# DE-160724.net
KiCad netlist of a schematic drawn in Altium Designer
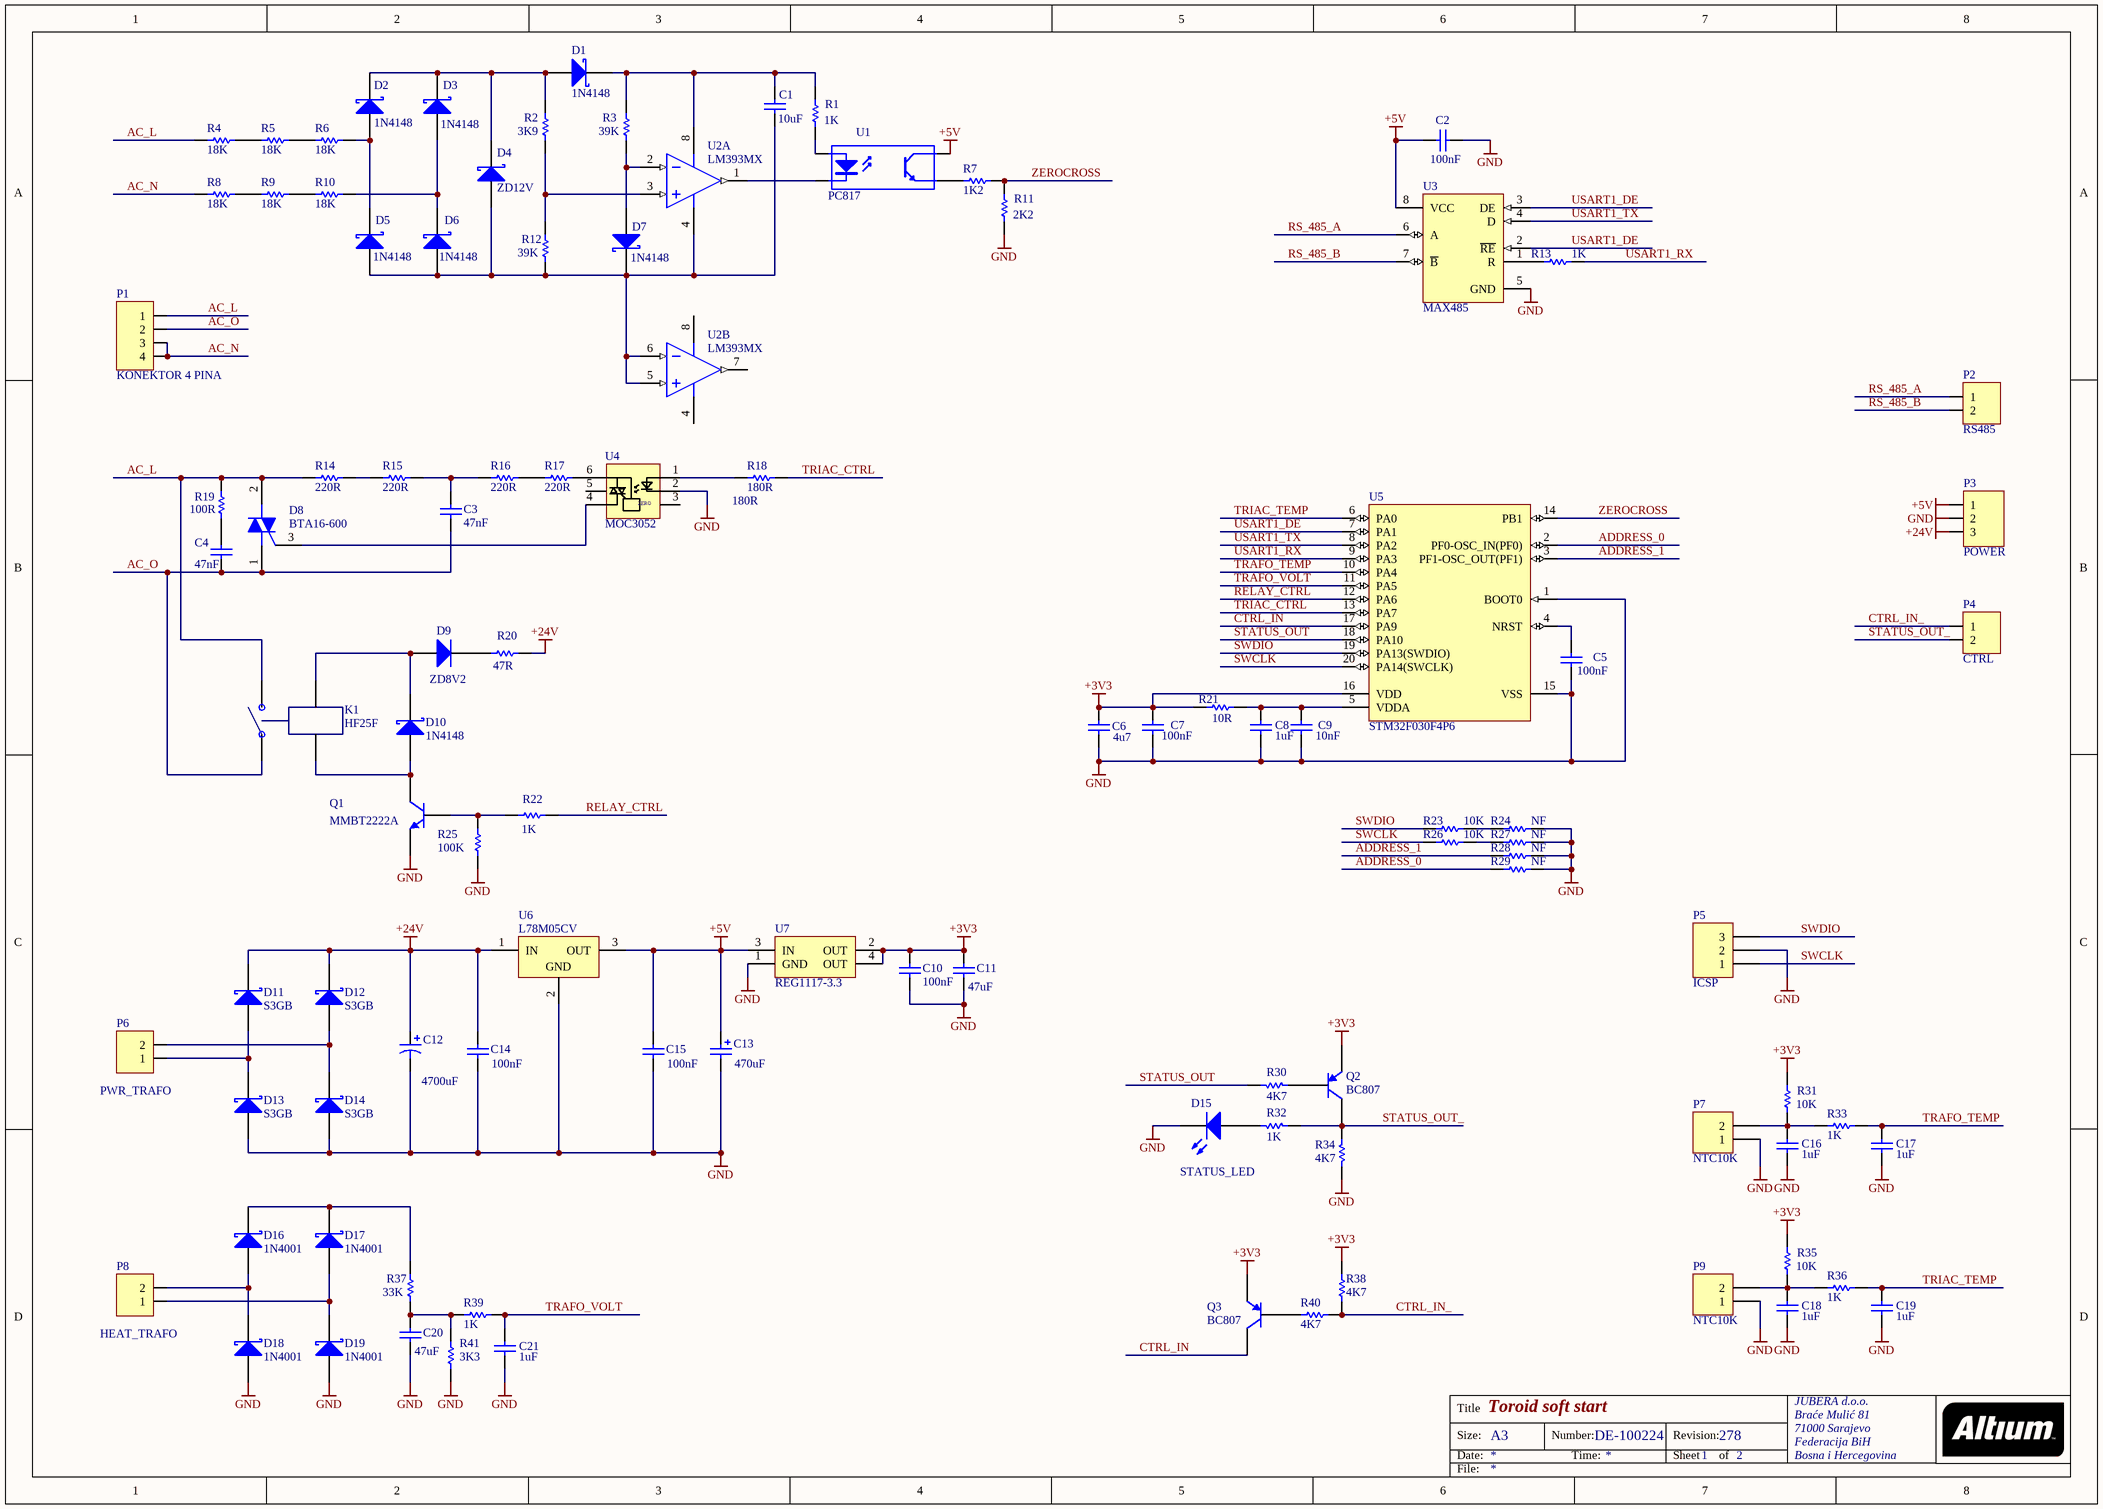
[diagram p0: DE-160724.SchDoc]

(export (version "E")
  (design (tool "Eeschema 10.0.6"))
  (components
    (comp (ref "C1")
      (value "10uF")
      (footprint "0805")
      (description "Ceramic Chip Capacitor - Standard")
      (fields (field (name "PUBLISHER") "Altium Limited"))
      (libsource (lib "DE-100224") (part "C0805"))
    )
    (comp (ref "C2")
      (value "100nF")
      (footprint "0603")
      (description "Ceramic Chip Capacitor - Standard")
      (fields (field (name "PUBLISHER") "Altium Limited"))
      (libsource (lib "KEMET Chip Capacitor") (part "C0603"))
    )
    (comp (ref "C3")
      (value "47nF")
      (footprint "X2 CAP")
      (description "X2 275VAC capaitor")
      (libsource (lib "DE-100224") (part "CAP X2"))
    )
    (comp (ref "C4")
      (value "47nF")
      (footprint "X2 CAP")
      (description "X2 275VAC capaitor")
      (libsource (lib "DE-100224") (part "CAP X2"))
    )
    (comp (ref "C5")
      (value "100nF")
      (footprint "0603")
      (description "Ceramic Chip Capacitor - Standard")
      (fields (field (name "PUBLISHER") "Altium Limited"))
      (libsource (lib "KEMET Chip Capacitor") (part "C0603"))
    )
    (comp (ref "C6")
      (value "4u7")
      (footprint "0805")
      (description "Ceramic Chip Capacitor - Standard")
      (fields (field (name "PUBLISHER") "Altium Limited"))
      (libsource (lib "KEMET Chip Capacitor") (part "C0805"))
    )
    (comp (ref "C7")
      (value "100nF")
      (footprint "0603")
      (description "Ceramic Chip Capacitor - Standard")
      (fields (field (name "PUBLISHER") "Altium Limited"))
      (libsource (lib "KEMET Chip Capacitor") (part "C0603"))
    )
    (comp (ref "C8")
      (value "1uF")
      (footprint "0603")
      (description "Ceramic Chip Capacitor - Standard")
      (fields (field (name "PUBLISHER") "Altium Limited"))
      (libsource (lib "KEMET Chip Capacitor") (part "C0603"))
    )
    (comp (ref "C9")
      (value "10nF")
      (footprint "0603")
      (description "Ceramic Chip Capacitor - Standard")
      (fields (field (name "PUBLISHER") "Altium Limited"))
      (libsource (lib "KEMET Chip Capacitor") (part "C0603"))
    )
    (comp (ref "C10")
      (value "100nF")
      (footprint "0603")
      (description "Ceramic Chip Capacitor - Standard")
      (fields (field (name "PUBLISHER") "Altium Limited"))
      (libsource (lib "DE-251215") (part "C0603"))
    )
    (comp (ref "C11")
      (value "47uF")
      (footprint "1206")
      (description "Ceramic Chip Capacitor - Standard")
      (fields (field (name "Comment") "C1206") (field (name "PUBLISHER") "Altium Limited"))
      (libsource (lib "DE-160724") (part "C1206"))
    )
    (comp (ref "C12")
      (value "4700uF")
      (footprint "CAPPR5-13X25")
      (description "Aluminum Electrolytic Capacitor, Radial Style with Long Leads: 4700uF, 10V")
      (fields (field (name "PUBLISHER") "Altium Limited"))
      (libsource (lib "Vishay Roederstein Electrolytic Radial-Lead Capacitor") (part "EKA00GG447C00"))
    )
    (comp (ref "C13")
      (value "470uF")
      (footprint "CAPPR5-10X16")
      (description "Aluminum Electrolytic Capacitor, Radial Style with Long Leads: 470uF, 35V")
      (fields (field (name "PUBLISHER") "Altium Limited"))
      (libsource (lib "DE-100224") (part "EKA00DD347F00"))
    )
    (comp (ref "C14")
      (value "100nF")
      (footprint "0603")
      (description "Ceramic Chip Capacitor - Standard")
      (fields (field (name "PUBLISHER") "Altium Limited"))
      (libsource (lib "DE-100224") (part "C0603"))
    )
    (comp (ref "C15")
      (value "100nF")
      (footprint "0603")
      (description "Ceramic Chip Capacitor - Standard")
      (fields (field (name "PUBLISHER") "Altium Limited"))
      (libsource (lib "DE-100224") (part "C0603"))
    )
    (comp (ref "C16")
      (value "1uF")
      (footprint "0603")
      (description "Ceramic Chip Capacitor - Standard")
      (fields (field (name "PUBLISHER") "Altium Limited"))
      (libsource (lib "KEMET Chip Capacitor") (part "C0603"))
    )
    (comp (ref "C17")
      (value "1uF")
      (footprint "0603")
      (description "Ceramic Chip Capacitor - Standard")
      (fields (field (name "PUBLISHER") "Altium Limited"))
      (libsource (lib "KEMET Chip Capacitor") (part "C0603"))
    )
    (comp (ref "C18")
      (value "1uF")
      (footprint "0603")
      (description "Ceramic Chip Capacitor - Standard")
      (fields (field (name "PUBLISHER") "Altium Limited"))
      (libsource (lib "KEMET Chip Capacitor") (part "C0603"))
    )
    (comp (ref "C19")
      (value "1uF")
      (footprint "0603")
      (description "Ceramic Chip Capacitor - Standard")
      (fields (field (name "PUBLISHER") "Altium Limited"))
      (libsource (lib "KEMET Chip Capacitor") (part "C0603"))
    )
    (comp (ref "C20")
      (value "47uF")
      (footprint "1206")
      (description "Ceramic Chip Capacitor - Standard")
      (fields (field (name "Comment") "C1206") (field (name "PUBLISHER") "Altium Limited"))
      (libsource (lib "DE-160724") (part "C1206"))
    )
    (comp (ref "C21")
      (value "1uF")
      (footprint "0603")
      (description "Ceramic Chip Capacitor - Standard")
      (fields (field (name "PUBLISHER") "Altium Limited"))
      (libsource (lib "KEMET Chip Capacitor") (part "C0603"))
    )
    (comp (ref "D1")
      (value "1N4148")
      (footprint "SOD323")
      (description "Schottky Barrier Diode")
      (fields (field (name "PUBLISHER") "Altium Limited"))
      (libsource (lib "DE-100224") (part "1PS76SB10"))
    )
    (comp (ref "D2")
      (value "1N4148")
      (footprint "SOD323")
      (description "Schottky Barrier Diode")
      (fields (field (name "PUBLISHER") "Altium Limited"))
      (libsource (lib "DE-100224") (part "1PS76SB10"))
    )
    (comp (ref "D3")
      (value "1N4148")
      (footprint "SOD323")
      (description "Schottky Barrier Diode")
      (fields (field (name "PUBLISHER") "Altium Limited"))
      (libsource (lib "DE-100224") (part "1PS76SB10"))
    )
    (comp (ref "D4")
      (value "ZD12V")
      (footprint "SMB")
      (description "Schottky Rectifier")
      (fields (field (name "PUBLISHER") "Altium Limited"))
      (libsource (lib "DE-100224") (part "10BQ100"))
    )
    (comp (ref "D5")
      (value "1N4148")
      (footprint "SOD323")
      (description "Schottky Barrier Diode")
      (fields (field (name "PUBLISHER") "Altium Limited"))
      (libsource (lib "DE-100224") (part "1PS76SB10"))
    )
    (comp (ref "D6")
      (value "1N4148")
      (footprint "SOD323")
      (description "Schottky Barrier Diode")
      (fields (field (name "PUBLISHER") "Altium Limited"))
      (libsource (lib "DE-100224") (part "1PS76SB10"))
    )
    (comp (ref "D7")
      (value "1N4148")
      (footprint "SOD323")
      (description "Schottky Barrier Diode")
      (fields (field (name "PUBLISHER") "Altium Limited"))
      (libsource (lib "DE-100224") (part "1PS76SB10"))
    )
    (comp (ref "D8")
      (value "BTA16-600")
      (footprint "ONSC-TO-220-3-221A-07")
      (description "Triacs, Silicon Bidirectional Thyristor, 3-Pin TO-220, Pb-Free, Tube")
      (fields (field (name "MANUFACTURER") "On Semiconductor") (field (name "PARTNUMBER") "BTA08-600BW3G"))
      (libsource (lib "DE-100224") (part "BTA08-600BW3G"))
    )
    (comp (ref "D9")
      (value "ZD8V2")
      (footprint "DO-41")
      (description "1.0 Ampere General Purpose Rectifier")
      (fields (field (name "PUBLISHER") "Altium Limited"))
      (libsource (lib "DE-100224") (part "1N4003"))
    )
    (comp (ref "D10")
      (value "1N4148")
      (footprint "SOD323")
      (description "Schottky Barrier Diode")
      (fields (field (name "PUBLISHER") "Altium Limited"))
      (libsource (lib "DE-100224") (part "1PS76SB10"))
    )
    (comp (ref "D11")
      (value "S3GB")
      (footprint "SMB")
      (description "Schottky Diode")
      (fields (field (name "PUBLISHER") "Altium Limited"))
      (libsource (lib "Miscellaneous Devices") (part "D Schottky"))
    )
    (comp (ref "D12")
      (value "S3GB")
      (footprint "SMB")
      (description "Schottky Diode")
      (fields (field (name "PUBLISHER") "Altium Limited"))
      (libsource (lib "Miscellaneous Devices") (part "D Schottky"))
    )
    (comp (ref "D13")
      (value "S3GB")
      (footprint "SMB")
      (description "Schottky Diode")
      (fields (field (name "PUBLISHER") "Altium Limited"))
      (libsource (lib "Miscellaneous Devices") (part "D Schottky"))
    )
    (comp (ref "D14")
      (value "S3GB")
      (footprint "SMB")
      (description "Schottky Diode")
      (fields (field (name "PUBLISHER") "Altium Limited"))
      (libsource (lib "Miscellaneous Devices") (part "D Schottky"))
    )
    (comp (ref "D15")
      (value "STATUS_LED")
      (footprint "1.6X0.8X0.8")
      (description "Blue Surface Mount Chip LED, Blue")
      (fields (field (name "PUBLISHER") "Altium Limited"))
      (libsource (lib "DE-160724") (part "HSMB-C190"))
    )
    (comp (ref "D16")
      (value "1N4001")
      (footprint "SMB")
      (description "Schottky Diode")
      (fields (field (name "PUBLISHER") "Altium Limited"))
      (libsource (lib "Miscellaneous Devices") (part "D Schottky"))
    )
    (comp (ref "D17")
      (value "1N4001")
      (footprint "SMB")
      (description "Schottky Diode")
      (fields (field (name "PUBLISHER") "Altium Limited"))
      (libsource (lib "Miscellaneous Devices") (part "D Schottky"))
    )
    (comp (ref "D18")
      (value "1N4001")
      (footprint "SMB")
      (description "Schottky Diode")
      (fields (field (name "PUBLISHER") "Altium Limited"))
      (libsource (lib "Miscellaneous Devices") (part "D Schottky"))
    )
    (comp (ref "D19")
      (value "1N4001")
      (footprint "SMB")
      (description "Schottky Diode")
      (fields (field (name "PUBLISHER") "Altium Limited"))
      (libsource (lib "Miscellaneous Devices") (part "D Schottky"))
    )
    (comp (ref "K1")
      (value "HF25F")
      (footprint "HF25F")
      (description "PCB relay 250VAC/20A 30VDC/16A")
      (libsource (lib "DE-100224") (part "HF25F"))
    )
    (comp (ref "P1")
      (value "KONEKTOR 4 PINA")
      (footprint "KONEKTOR 4 PINA")
      (description "Razdvojivi konektor 4 pina")
      (libsource (lib "DE-100224") (part "KONEKTOR 4 PINA"))
    )
    (comp (ref "P2")
      (value "RS485")
      (footprint "TERMINAL BLOK 2")
      (description "Terminal blok konektor 3,5 mm")
      (libsource (lib "DE-160724") (part "TERMINAL BLOK 2"))
    )
    (comp (ref "P3")
      (value "POWER")
      (footprint "TERMINAL BLOK 3")
      (description "3 pinski terminal blok konektor")
      (libsource (lib "DE-100224") (part "TERMINAL BLOK 3"))
    )
    (comp (ref "P4")
      (value "CTRL")
      (footprint "TERMINAL BLOK 2")
      (description "Terminal blok konektor 3,5 mm")
      (libsource (lib "DE-160724") (part "TERMINAL BLOK 2"))
    )
    (comp (ref "P5")
      (value "ICSP")
      (footprint "HDR1X3")
      (description "Header, 3-Pin")
      (fields (field (name "PUBLISHER") "Altium Limited"))
      (libsource (lib "Miscellaneous Connectors") (part "Header 3"))
    )
    (comp (ref "P6")
      (value "PWR_TRAFO")
      (footprint "KONEKTOR 2 PINA")
      (description "Razdvojivi konetor 2 pina")
      (libsource (lib "DE-100224") (part "KONEKTOR 2 PINA"))
    )
    (comp (ref "P7")
      (value "NTC10K")
      (footprint "HDR1X2")
      (description "Header, 2-Pin")
      (fields (field (name "PUBLISHER") "Altium Limited"))
      (libsource (lib "Miscellaneous Connectors") (part "Header 2"))
    )
    (comp (ref "P8")
      (value "HEAT_TRAFO")
      (footprint "KONEKTOR 2 PINA")
      (description "Razdvojivi konetor 2 pina")
      (libsource (lib "DE-100224") (part "KONEKTOR 2 PINA"))
    )
    (comp (ref "P9")
      (value "NTC10K")
      (footprint "HDR1X2")
      (description "Header, 2-Pin")
      (fields (field (name "PUBLISHER") "Altium Limited"))
      (libsource (lib "Miscellaneous Connectors") (part "Header 2"))
    )
    (comp (ref "Q1")
      (value "MMBT2222A")
      (footprint "SOT23_N")
      (description "NPN General-purpose Transistor")
      (fields (field (name "PUBLISHER") "Altium Limited"))
      (libsource (lib "DE-100224") (part "BC817"))
    )
    (comp (ref "Q2")
      (value "BC807")
      (footprint "SOT23_N")
      (description "PNP General-purpose Transistor")
      (fields (field (name "PUBLISHER") "Altium Limited"))
      (libsource (lib "DE-160724") (part "BC807"))
    )
    (comp (ref "Q3")
      (value "BC807")
      (footprint "SOT23_N")
      (description "PNP General-purpose Transistor")
      (fields (field (name "PUBLISHER") "Altium Limited"))
      (libsource (lib "DE-160724") (part "BC807"))
    )
    (comp (ref "R1")
      (value "1K")
      (footprint "ERA-0603")
      (fields (field (name "PUBLISHER") "Altium Limited"))
      (libsource (lib "DE-100224") (part "ERAV"))
    )
    (comp (ref "R2")
      (value "3K9")
      (footprint "ERA-0603")
      (fields (field (name "PUBLISHER") "Altium Limited"))
      (libsource (lib "DE-100224") (part "ERAV"))
    )
    (comp (ref "R3")
      (value "39K")
      (footprint "ERA-0603")
      (fields (field (name "PUBLISHER") "Altium Limited"))
      (libsource (lib "DE-100224") (part "ERAV"))
    )
    (comp (ref "R4")
      (value "18K")
      (footprint "ERA-0805")
      (fields (field (name "PUBLISHER") "Altium Limited"))
      (libsource (lib "DE-100224") (part "ERAS"))
    )
    (comp (ref "R5")
      (value "18K")
      (footprint "ERA-0805")
      (fields (field (name "PUBLISHER") "Altium Limited"))
      (libsource (lib "DE-100224") (part "ERAS"))
    )
    (comp (ref "R6")
      (value "18K")
      (footprint "ERA-0805")
      (fields (field (name "PUBLISHER") "Altium Limited"))
      (libsource (lib "DE-100224") (part "ERAS"))
    )
    (comp (ref "R7")
      (value "1K2")
      (footprint "ERA-0603")
      (fields (field (name "PUBLISHER") "Altium Limited"))
      (libsource (lib "DE-100224") (part "ERAV"))
    )
    (comp (ref "R8")
      (value "18K")
      (footprint "ERA-0805")
      (fields (field (name "PUBLISHER") "Altium Limited"))
      (libsource (lib "DE-100224") (part "ERAS"))
    )
    (comp (ref "R9")
      (value "18K")
      (footprint "ERA-0805")
      (fields (field (name "PUBLISHER") "Altium Limited"))
      (libsource (lib "DE-100224") (part "ERAS"))
    )
    (comp (ref "R10")
      (value "18K")
      (footprint "ERA-0805")
      (fields (field (name "PUBLISHER") "Altium Limited"))
      (libsource (lib "DE-100224") (part "ERAS"))
    )
    (comp (ref "R11")
      (value "2K2")
      (footprint "ERA-0603")
      (fields (field (name "PUBLISHER") "Altium Limited"))
      (libsource (lib "DE-100224") (part "ERAV"))
    )
    (comp (ref "R12")
      (value "39K")
      (footprint "ERA-0603")
      (fields (field (name "PUBLISHER") "Altium Limited"))
      (libsource (lib "DE-100224") (part "ERAV"))
    )
    (comp (ref "R13")
      (value "1K")
      (footprint "ERA-0603")
      (fields (field (name "PUBLISHER") "Altium Limited"))
      (libsource (lib "DE-280817") (part "ERA6Y"))
    )
    (comp (ref "R14")
      (value "220R")
      (footprint "ERA-0805")
      (fields (field (name "PUBLISHER") "Altium Limited"))
      (libsource (lib "DE-100224") (part "ERAS"))
    )
    (comp (ref "R15")
      (value "220R")
      (footprint "ERA-0805")
      (fields (field (name "PUBLISHER") "Altium Limited"))
      (libsource (lib "DE-100224") (part "ERAS"))
    )
    (comp (ref "R16")
      (value "220R")
      (footprint "ERA-0805")
      (fields (field (name "PUBLISHER") "Altium Limited"))
      (libsource (lib "DE-100224") (part "ERAS"))
    )
    (comp (ref "R17")
      (value "220R")
      (footprint "ERA-0805")
      (fields (field (name "PUBLISHER") "Altium Limited"))
      (libsource (lib "DE-100224") (part "ERAS"))
    )
    (comp (ref "R18")
      (value "180R")
      (footprint "ERA-0603")
      (fields (field (name "ALTIUM_VALUE") "180R") (field (name "PUBLISHER") "Altium Limited"))
      (libsource (lib "DE-100224") (part "ERAV"))
    )
    (comp (ref "R19")
      (value "100R")
      (footprint "1W100R")
      (description "Carbon F 1W resistor")
      (fields (field (name "PUBLISHER") "Altium Limited"))
      (libsource (lib "DE-100224") (part "1W100R"))
    )
    (comp (ref "R20")
      (value "47R")
      (footprint "AXIAL-0.3")
      (description "Resistor")
      (fields (field (name "PUBLISHER") "Altium Limited"))
      (libsource (lib "Miscellaneous Devices") (part "Res1"))
    )
    (comp (ref "R21")
      (value "10R")
      (footprint "ERA-0603")
      (fields (field (name "PUBLISHER") "Altium Limited"))
      (libsource (lib "DE-280817") (part "ERA6Y"))
    )
    (comp (ref "R22")
      (value "1K")
      (footprint "ERA-0603")
      (fields (field (name "PUBLISHER") "Altium Limited"))
      (libsource (lib "DE-100224") (part "ERAV"))
    )
    (comp (ref "R23")
      (value "10K")
      (footprint "ERA-0603")
      (fields (field (name "PUBLISHER") "Altium Limited"))
      (libsource (lib "DE-280817") (part "ERA6Y"))
    )
    (comp (ref "R24")
      (value "NF")
      (footprint "ERA-0603")
      (fields (field (name "PUBLISHER") "Altium Limited"))
      (libsource (lib "DE-280817") (part "ERA6Y"))
    )
    (comp (ref "R25")
      (value "100K")
      (footprint "ERA-0603")
      (fields (field (name "PUBLISHER") "Altium Limited"))
      (libsource (lib "DE-100224") (part "ERAV"))
    )
    (comp (ref "R26")
      (value "10K")
      (footprint "ERA-0603")
      (fields (field (name "PUBLISHER") "Altium Limited"))
      (libsource (lib "DE-280817") (part "ERA6Y"))
    )
    (comp (ref "R27")
      (value "NF")
      (footprint "ERA-0603")
      (fields (field (name "PUBLISHER") "Altium Limited"))
      (libsource (lib "DE-280817") (part "ERA6Y"))
    )
    (comp (ref "R28")
      (value "NF")
      (footprint "ERA-0603")
      (fields (field (name "PUBLISHER") "Altium Limited"))
      (libsource (lib "DE-280817") (part "ERA6Y"))
    )
    (comp (ref "R29")
      (value "NF")
      (footprint "ERA-0603")
      (fields (field (name "PUBLISHER") "Altium Limited"))
      (libsource (lib "DE-280817") (part "ERA6Y"))
    )
    (comp (ref "R30")
      (value "4K7")
      (footprint "ERA-0603")
      (fields (field (name "PUBLISHER") "Altium Limited"))
      (libsource (lib "DE-280817") (part "ERA6Y"))
    )
    (comp (ref "R31")
      (value "10K")
      (footprint "ERA-0603")
      (fields (field (name "PUBLISHER") "Altium Limited"))
      (libsource (lib "DE-100224") (part "ERAV"))
    )
    (comp (ref "R32")
      (value "1K")
      (footprint "ERA-0603")
      (fields (field (name "PUBLISHER") "Altium Limited"))
      (libsource (lib "DE-280817") (part "ERA6Y"))
    )
    (comp (ref "R33")
      (value "1K")
      (footprint "ERA-0603")
      (fields (field (name "PUBLISHER") "Altium Limited"))
      (libsource (lib "DE-100224") (part "ERAV"))
    )
    (comp (ref "R34")
      (value "4K7")
      (footprint "ERA-0603")
      (fields (field (name "PUBLISHER") "Altium Limited"))
      (libsource (lib "DE-280817") (part "ERA6Y"))
    )
    (comp (ref "R35")
      (value "10K")
      (footprint "ERA-0603")
      (fields (field (name "PUBLISHER") "Altium Limited"))
      (libsource (lib "DE-100224") (part "ERAV"))
    )
    (comp (ref "R36")
      (value "1K")
      (footprint "ERA-0603")
      (fields (field (name "PUBLISHER") "Altium Limited"))
      (libsource (lib "DE-100224") (part "ERAV"))
    )
    (comp (ref "R37")
      (value "33K")
      (footprint "ERA-0603")
      (fields (field (name "PUBLISHER") "Altium Limited"))
      (libsource (lib "DE-100224") (part "ERAV"))
    )
    (comp (ref "R38")
      (value "4K7")
      (footprint "ERA-0603")
      (fields (field (name "PUBLISHER") "Altium Limited"))
      (libsource (lib "DE-280817") (part "ERA6Y"))
    )
    (comp (ref "R39")
      (value "1K")
      (footprint "ERA-0603")
      (fields (field (name "PUBLISHER") "Altium Limited"))
      (libsource (lib "DE-100224") (part "ERAV"))
    )
    (comp (ref "R40")
      (value "4K7")
      (footprint "ERA-0603")
      (fields (field (name "PUBLISHER") "Altium Limited"))
      (libsource (lib "DE-280817") (part "ERA6Y"))
    )
    (comp (ref "R41")
      (value "3K3")
      (footprint "ERA-0603")
      (fields (field (name "PUBLISHER") "Altium Limited"))
      (libsource (lib "DE-100224") (part "ERAV"))
    )
    (comp (ref "U1")
      (value "PC817")
      (footprint "DIP-4")
      (description "4-Pin Phototransistor Optocoupler")
      (fields (field (name "PUBLISHER") "Altium Limited"))
      (libsource (lib "DE-100224") (part "PC817"))
    )
    (comp (ref "U2")
      (value "LM393MX")
      (footprint "M08A_N")
      (description "Low Power Low Offset Voltage Dual Comparator, 8-pin Narrow SOIC")
      (fields (field (name "MANUFACTURER") "National Semiconductor"))
      (libsource (lib "National Semiconductor Comparator") (part "LM393MX"))
    )
    (comp (ref "U3")
      (value "MAX485")
      (footprint "D008_L")
      (description "Differential Bus Transceiver")
      (fields (field (name "PUBLISHER") "Altium Limited"))
      (libsource (lib "DE-280817") (part "SN75176BD"))
    )
    (comp (ref "U4")
      (value "MOC3052")
      (footprint "DIP6")
      (description "Zero-Cross Optoisolator Triac Driver")
      (libsource (lib "DE-100224") (part "MOC3081"))
    )
    (comp (ref "U5")
      (value "STM32F030F4P6")
      (footprint "STM-TSSOP20_N")
      (libsource (lib "STMicroelectronics STM32 F0") (part "STM32F030F4P6"))
    )
    (comp (ref "U6")
      (value "L78M05CV")
      (footprint "TO220")
      (description "Positive Voltage Regulator, 5V, 3-Pin TO-220")
      (libsource (lib "STMicroelectronics Power Management Linear Regulator") (part "L78M05CV"))
    )
    (comp (ref "U7")
      (value "REG1117-3.3")
      (footprint "ZZ311")
      (description "800mA and 1A Low Dropout Positive Regulator 2.85V, 3.3V, 5V, and Adjustable")
      (fields (field (name "PUBLISHER") "Altium Limited"))
      (libsource (lib "DE-251215") (part "REG1117-3.3"))
    )
  )
  (nets
    (net (code "1") (name "+3V3") (class "Default")
      (node (ref "C10") (pin "2") (pinfunction "2_2") (pintype "passive"))
      (node (ref "C11") (pin "2") (pinfunction "2_2") (pintype "passive"))
      (node (ref "C6") (pin "1") (pinfunction "1_1") (pintype "passive"))
      (node (ref "C7") (pin "1") (pinfunction "1_1") (pintype "passive"))
      (node (ref "Q2") (pin "2") (pinfunction "E_2") (pintype "passive"))
      (node (ref "Q3") (pin "2") (pinfunction "E_2") (pintype "passive"))
      (node (ref "R21") (pin "2") (pinfunction "2_2") (pintype "passive"))
      (node (ref "R31") (pin "2") (pinfunction "2_2") (pintype "passive"))
      (node (ref "R35") (pin "2") (pinfunction "2_2") (pintype "passive"))
      (node (ref "R38") (pin "1") (pinfunction "1_1") (pintype "passive"))
      (node (ref "U5") (pin "16") (pinfunction "VDD_16") (pintype "power_in"))
      (node (ref "U7") (pin "2") (pinfunction "OUT_2") (pintype "power_in"))
      (node (ref "U7") (pin "4") (pinfunction "OUT_4") (pintype "power_in"))
    )
    (net (code "2") (name "+5V") (class "Default")
      (node (ref "C13") (pin "1") (pinfunction "1_1") (pintype "passive"))
      (node (ref "C15") (pin "2") (pinfunction "2_2") (pintype "passive"))
      (node (ref "C2") (pin "1") (pinfunction "1_1") (pintype "passive"))
      (node (ref "P3") (pin "1") (pinfunction "1_1") (pintype "passive"))
      (node (ref "U1") (pin "4") (pinfunction "C_4") (pintype "passive"))
      (node (ref "U3") (pin "8") (pinfunction "VCC_8") (pintype "power_in"))
      (node (ref "U6") (pin "3") (pinfunction "OUT_3") (pintype "power_in"))
      (node (ref "U7") (pin "3") (pinfunction "IN_3") (pintype "power_in"))
    )
    (net (code "3") (name "+24V") (class "Default")
      (node (ref "C12") (pin "1") (pinfunction "1_1") (pintype "passive"))
      (node (ref "C14") (pin "2") (pinfunction "2_2") (pintype "passive"))
      (node (ref "D11") (pin "2") (pinfunction "K_2") (pintype "passive"))
      (node (ref "D12") (pin "2") (pinfunction "K_2") (pintype "passive"))
      (node (ref "P3") (pin "3") (pinfunction "3_3") (pintype "passive"))
      (node (ref "R20") (pin "2") (pinfunction "2_2") (pintype "passive"))
      (node (ref "U6") (pin "1") (pinfunction "IN_1") (pintype "power_in"))
    )
    (net (code "4") (name "/AC_L") (class "Default")
      (node (ref "D8") (pin "2") (pinfunction "MT2_2") (pintype "passive"))
      (node (ref "K1") (pin "4") (pinfunction "4_4") (pintype "passive"))
      (node (ref "P1") (pin "1") (pinfunction "1_1") (pintype "passive"))
      (node (ref "R14") (pin "1") (pinfunction "1_1") (pintype "passive"))
      (node (ref "R19") (pin "2") (pinfunction "2_2") (pintype "passive"))
      (node (ref "R4") (pin "1") (pinfunction "1_1") (pintype "passive"))
    )
    (net (code "5") (name "/AC_N") (class "Default")
      (node (ref "P1") (pin "3") (pinfunction "3_3") (pintype "passive"))
      (node (ref "P1") (pin "4") (pinfunction "4_4") (pintype "passive"))
      (node (ref "R8") (pin "1") (pinfunction "1_1") (pintype "passive"))
    )
    (net (code "6") (name "/AC_O") (class "Default")
      (node (ref "C3") (pin "1") (pinfunction "1_1") (pintype "passive"))
      (node (ref "C4") (pin "1") (pinfunction "1_1") (pintype "passive"))
      (node (ref "D8") (pin "1") (pinfunction "MT1_1") (pintype "passive"))
      (node (ref "K1") (pin "3") (pinfunction "3_3") (pintype "passive"))
      (node (ref "P1") (pin "2") (pinfunction "2_2") (pintype "passive"))
    )
    (net (code "7") (name "/ADDRESS_0") (class "Default")
      (node (ref "R29") (pin "2") (pinfunction "2_2") (pintype "passive"))
      (node (ref "U5") (pin "2") (pinfunction "PF0-OSC_IN(PF0)_2") (pintype "bidirectional"))
    )
    (net (code "8") (name "/ADDRESS_1") (class "Default")
      (node (ref "R28") (pin "2") (pinfunction "2_2") (pintype "passive"))
      (node (ref "U5") (pin "3") (pinfunction "PF1-OSC_OUT(PF1)_3") (pintype "bidirectional"))
    )
    (net (code "9") (name "/CTRL_IN") (class "Default")
      (node (ref "Q3") (pin "3") (pinfunction "C_3") (pintype "passive"))
      (node (ref "U5") (pin "17") (pinfunction "PA9_17") (pintype "bidirectional"))
    )
    (net (code "10") (name "/CTRL_IN_") (class "Default")
      (node (ref "P4") (pin "1") (pinfunction "1_1") (pintype "passive"))
      (node (ref "R38") (pin "2") (pinfunction "2_2") (pintype "passive"))
      (node (ref "R40") (pin "2") (pinfunction "2_2") (pintype "passive"))
    )
    (net (code "11") (name "/RELAY_CTRL") (class "Default")
      (node (ref "R22") (pin "1") (pinfunction "1_1") (pintype "passive"))
      (node (ref "U5") (pin "12") (pinfunction "PA6_12") (pintype "bidirectional"))
    )
    (net (code "12") (name "/RS_485_A") (class "Default")
      (node (ref "P2") (pin "1") (pinfunction "1_1") (pintype "passive"))
      (node (ref "U3") (pin "6") (pinfunction "A_6") (pintype "bidirectional"))
    )
    (net (code "13") (name "/RS_485_B") (class "Default")
      (node (ref "P2") (pin "2") (pinfunction "2_2") (pintype "passive"))
      (node (ref "U3") (pin "7") (pinfunction "~{B}_7") (pintype "bidirectional"))
    )
    (net (code "14") (name "/STATUS_OUT") (class "Default")
      (node (ref "R30") (pin "2") (pinfunction "2_2") (pintype "passive"))
      (node (ref "U5") (pin "18") (pinfunction "PA10_18") (pintype "bidirectional"))
    )
    (net (code "15") (name "/STATUS_OUT_") (class "Default")
      (node (ref "P4") (pin "2") (pinfunction "2_2") (pintype "passive"))
      (node (ref "Q2") (pin "3") (pinfunction "C_3") (pintype "passive"))
      (node (ref "R32") (pin "1") (pinfunction "1_1") (pintype "passive"))
      (node (ref "R34") (pin "1") (pinfunction "1_1") (pintype "passive"))
    )
    (net (code "16") (name "/SWCLK") (class "Default")
      (node (ref "P5") (pin "1") (pinfunction "1_1") (pintype "passive"))
      (node (ref "R26") (pin "2") (pinfunction "2_2") (pintype "passive"))
      (node (ref "U5") (pin "20") (pinfunction "PA14(SWCLK)_20") (pintype "bidirectional"))
    )
    (net (code "17") (name "/SWDIO") (class "Default")
      (node (ref "P5") (pin "3") (pinfunction "3_3") (pintype "passive"))
      (node (ref "R23") (pin "2") (pinfunction "2_2") (pintype "passive"))
      (node (ref "U5") (pin "19") (pinfunction "PA13(SWDIO)_19") (pintype "bidirectional"))
    )
    (net (code "18") (name "/TRAFO_TEMP") (class "Default")
      (node (ref "C17") (pin "1") (pinfunction "1_1") (pintype "passive"))
      (node (ref "R33") (pin "1") (pinfunction "1_1") (pintype "passive"))
      (node (ref "U5") (pin "10") (pinfunction "PA4_10") (pintype "bidirectional"))
    )
    (net (code "19") (name "/TRAFO_VOLT") (class "Default")
      (node (ref "C21") (pin "1") (pinfunction "1_1") (pintype "passive"))
      (node (ref "R39") (pin "1") (pinfunction "1_1") (pintype "passive"))
      (node (ref "U5") (pin "11") (pinfunction "PA5_11") (pintype "bidirectional"))
    )
    (net (code "20") (name "/TRIAC_CTRL") (class "Default")
      (node (ref "R18") (pin "1") (pinfunction "1_1") (pintype "passive"))
      (node (ref "U5") (pin "13") (pinfunction "PA7_13") (pintype "bidirectional"))
    )
    (net (code "21") (name "/TRIAC_TEMP") (class "Default")
      (node (ref "C19") (pin "1") (pinfunction "1_1") (pintype "passive"))
      (node (ref "R36") (pin "1") (pinfunction "1_1") (pintype "passive"))
      (node (ref "U5") (pin "6") (pinfunction "PA0_6") (pintype "bidirectional"))
    )
    (net (code "22") (name "/USART1_DE") (class "Default")
      (node (ref "U3") (pin "2") (pinfunction "~{RE}_2") (pintype "input"))
      (node (ref "U3") (pin "3") (pinfunction "DE_3") (pintype "input"))
      (node (ref "U5") (pin "7") (pinfunction "PA1_7") (pintype "bidirectional"))
    )
    (net (code "23") (name "/USART1_RX") (class "Default")
      (node (ref "R13") (pin "1") (pinfunction "1_1") (pintype "passive"))
      (node (ref "U5") (pin "9") (pinfunction "PA3_9") (pintype "bidirectional"))
    )
    (net (code "24") (name "/USART1_TX") (class "Default")
      (node (ref "U3") (pin "4") (pinfunction "D_4") (pintype "input"))
      (node (ref "U5") (pin "8") (pinfunction "PA2_8") (pintype "bidirectional"))
    )
    (net (code "25") (name "/ZEROCROSS") (class "Default")
      (node (ref "R11") (pin "2") (pinfunction "2_2") (pintype "passive"))
      (node (ref "R7") (pin "1") (pinfunction "1_1") (pintype "passive"))
      (node (ref "U5") (pin "14") (pinfunction "PB1_14") (pintype "bidirectional"))
    )
    (net (code "26") (name "GND") (class "Default")
      (node (ref "C10") (pin "1") (pinfunction "1_1") (pintype "passive"))
      (node (ref "C11") (pin "1") (pinfunction "1_1") (pintype "passive"))
      (node (ref "C12") (pin "2") (pinfunction "2_2") (pintype "passive"))
      (node (ref "C13") (pin "2") (pinfunction "2_2") (pintype "passive"))
      (node (ref "C14") (pin "1") (pinfunction "1_1") (pintype "passive"))
      (node (ref "C15") (pin "1") (pinfunction "1_1") (pintype "passive"))
      (node (ref "C16") (pin "2") (pinfunction "2_2") (pintype "passive"))
      (node (ref "C17") (pin "2") (pinfunction "2_2") (pintype "passive"))
      (node (ref "C18") (pin "2") (pinfunction "2_2") (pintype "passive"))
      (node (ref "C19") (pin "2") (pinfunction "2_2") (pintype "passive"))
      (node (ref "C2") (pin "2") (pinfunction "2_2") (pintype "passive"))
      (node (ref "C20") (pin "1") (pinfunction "1_1") (pintype "passive"))
      (node (ref "C21") (pin "2") (pinfunction "2_2") (pintype "passive"))
      (node (ref "C5") (pin "2") (pinfunction "2_2") (pintype "passive"))
      (node (ref "C6") (pin "2") (pinfunction "2_2") (pintype "passive"))
      (node (ref "C7") (pin "2") (pinfunction "2_2") (pintype "passive"))
      (node (ref "C8") (pin "2") (pinfunction "2_2") (pintype "passive"))
      (node (ref "C9") (pin "2") (pinfunction "2_2") (pintype "passive"))
      (node (ref "D13") (pin "1") (pinfunction "A_1") (pintype "passive"))
      (node (ref "D14") (pin "1") (pinfunction "A_1") (pintype "passive"))
      (node (ref "D15") (pin "2") (pinfunction "K_2") (pintype "passive"))
      (node (ref "D18") (pin "1") (pinfunction "A_1") (pintype "passive"))
      (node (ref "D19") (pin "1") (pinfunction "A_1") (pintype "passive"))
      (node (ref "P3") (pin "2") (pinfunction "2_2") (pintype "passive"))
      (node (ref "P5") (pin "2") (pinfunction "2_2") (pintype "passive"))
      (node (ref "P7") (pin "1") (pinfunction "1_1") (pintype "passive"))
      (node (ref "P9") (pin "1") (pinfunction "1_1") (pintype "passive"))
      (node (ref "Q1") (pin "2") (pinfunction "E_2") (pintype "passive"))
      (node (ref "R11") (pin "1") (pinfunction "1_1") (pintype "passive"))
      (node (ref "R24") (pin "1") (pinfunction "1_1") (pintype "passive"))
      (node (ref "R25") (pin "1") (pinfunction "1_1") (pintype "passive"))
      (node (ref "R27") (pin "1") (pinfunction "1_1") (pintype "passive"))
      (node (ref "R28") (pin "1") (pinfunction "1_1") (pintype "passive"))
      (node (ref "R29") (pin "1") (pinfunction "1_1") (pintype "passive"))
      (node (ref "R34") (pin "2") (pinfunction "2_2") (pintype "passive"))
      (node (ref "R41") (pin "1") (pinfunction "1_1") (pintype "passive"))
      (node (ref "U3") (pin "5") (pinfunction "GND_5") (pintype "power_in"))
      (node (ref "U4") (pin "2") (pinfunction "2_2") (pintype "passive"))
      (node (ref "U5") (pin "1") (pinfunction "BOOT0_1") (pintype "input"))
      (node (ref "U5") (pin "15") (pinfunction "VSS_15") (pintype "power_in"))
      (node (ref "U6") (pin "2") (pinfunction "GND_2") (pintype "power_in"))
      (node (ref "U7") (pin "1") (pinfunction "GND_1") (pintype "power_in"))
    )
    (net (code "27") (name "Net-(C3-Pad2)") (class "Default")
      (node (ref "C3") (pin "2") (pinfunction "2_2") (pintype "passive"))
      (node (ref "R15") (pin "2") (pinfunction "2_2") (pintype "passive"))
      (node (ref "R16") (pin "1") (pinfunction "1_1") (pintype "passive"))
    )
    (net (code "28") (name "Net-(C4-Pad2)") (class "Default")
      (node (ref "C4") (pin "2") (pinfunction "2_2") (pintype "passive"))
      (node (ref "R19") (pin "1") (pinfunction "1_1") (pintype "passive"))
    )
    (net (code "29") (name "Net-(C16-Pad1)") (class "Default")
      (node (ref "C16") (pin "1") (pinfunction "1_1") (pintype "passive"))
      (node (ref "P7") (pin "2") (pinfunction "2_2") (pintype "passive"))
      (node (ref "R31") (pin "1") (pinfunction "1_1") (pintype "passive"))
      (node (ref "R33") (pin "2") (pinfunction "2_2") (pintype "passive"))
    )
    (net (code "30") (name "Net-(C18-Pad1)") (class "Default")
      (node (ref "C18") (pin "1") (pinfunction "1_1") (pintype "passive"))
      (node (ref "P9") (pin "2") (pinfunction "2_2") (pintype "passive"))
      (node (ref "R35") (pin "1") (pinfunction "1_1") (pintype "passive"))
      (node (ref "R36") (pin "2") (pinfunction "2_2") (pintype "passive"))
    )
    (net (code "31") (name "Net-(C20-Pad2)") (class "Default")
      (node (ref "C20") (pin "2") (pinfunction "2_2") (pintype "passive"))
      (node (ref "R37") (pin "1") (pinfunction "1_1") (pintype "passive"))
      (node (ref "R39") (pin "2") (pinfunction "2_2") (pintype "passive"))
      (node (ref "R41") (pin "2") (pinfunction "2_2") (pintype "passive"))
    )
    (net (code "32") (name "Net-(D1-A)") (class "Default")
      (node (ref "D1") (pin "2") (pinfunction "A_2") (pintype "passive"))
      (node (ref "D2") (pin "1") (pinfunction "K_1") (pintype "passive"))
      (node (ref "D3") (pin "1") (pinfunction "K_1") (pintype "passive"))
      (node (ref "D4") (pin "2") (pinfunction "K_2") (pintype "passive"))
      (node (ref "R2") (pin "2") (pinfunction "2_2") (pintype "passive"))
    )
    (net (code "33") (name "Net-(D1-K)") (class "Default")
      (node (ref "C1") (pin "2") (pinfunction "2_2") (pintype "passive"))
      (node (ref "D1") (pin "1") (pinfunction "K_1") (pintype "passive"))
      (node (ref "R1") (pin "2") (pinfunction "2_2") (pintype "passive"))
      (node (ref "R3") (pin "2") (pinfunction "2_2") (pintype "passive"))
      (node (ref "U2") (pin "8") (pinfunction "V+_8") (pintype "power_in"))
    )
    (net (code "34") (name "Net-(D2-A)") (class "Default")
      (node (ref "D2") (pin "2") (pinfunction "A_2") (pintype "passive"))
      (node (ref "D5") (pin "1") (pinfunction "K_1") (pintype "passive"))
      (node (ref "R6") (pin "2") (pinfunction "2_2") (pintype "passive"))
    )
    (net (code "35") (name "Net-(D3-A)") (class "Default")
      (node (ref "D3") (pin "2") (pinfunction "A_2") (pintype "passive"))
      (node (ref "D6") (pin "1") (pinfunction "K_1") (pintype "passive"))
      (node (ref "R10") (pin "2") (pinfunction "2_2") (pintype "passive"))
    )
    (net (code "36") (name "Net-(D4-A)") (class "Default")
      (node (ref "C1") (pin "1") (pinfunction "1_1") (pintype "passive"))
      (node (ref "D4") (pin "1") (pinfunction "A_1") (pintype "passive"))
      (node (ref "D5") (pin "2") (pinfunction "A_2") (pintype "passive"))
      (node (ref "D6") (pin "2") (pinfunction "A_2") (pintype "passive"))
      (node (ref "D7") (pin "1") (pinfunction "K_1") (pintype "passive"))
      (node (ref "R12") (pin "1") (pinfunction "1_1") (pintype "passive"))
      (node (ref "U2") (pin "4") (pinfunction "GND_4") (pintype "power_in"))
      (node (ref "U2") (pin "5") (pinfunction "INB+_5") (pintype "input"))
      (node (ref "U2") (pin "6") (pinfunction "INB-_6") (pintype "input"))
    )
    (net (code "37") (name "Net-(D7-A)") (class "Default")
      (node (ref "D7") (pin "2") (pinfunction "A_2") (pintype "passive"))
      (node (ref "R3") (pin "1") (pinfunction "1_1") (pintype "passive"))
      (node (ref "U2") (pin "2") (pinfunction "INA-_2") (pintype "input"))
    )
    (net (code "38") (name "Net-(D8-G)") (class "Default")
      (node (ref "D8") (pin "3") (pinfunction "G_3") (pintype "passive"))
      (node (ref "U4") (pin "4") (pinfunction "4_4") (pintype "passive"))
    )
    (net (code "39") (name "Net-(D9-K)") (class "Default")
      (node (ref "D9") (pin "2") (pinfunction "K_2") (pintype "passive"))
      (node (ref "R20") (pin "1") (pinfunction "1_1") (pintype "passive"))
    )
    (net (code "40") (name "Net-(D10-A)") (class "Default")
      (node (ref "D10") (pin "2") (pinfunction "A_2") (pintype "passive"))
      (node (ref "K1") (pin "1") (pinfunction "1_1") (pintype "passive"))
      (node (ref "Q1") (pin "3") (pinfunction "C_3") (pintype "passive"))
    )
    (net (code "41") (name "Net-(D10-K)") (class "Default")
      (node (ref "D10") (pin "1") (pinfunction "K_1") (pintype "passive"))
      (node (ref "D9") (pin "1") (pinfunction "A_1") (pintype "passive"))
      (node (ref "K1") (pin "2") (pinfunction "2_2") (pintype "passive"))
    )
    (net (code "42") (name "Net-(D11-A)") (class "Default")
      (node (ref "D11") (pin "1") (pinfunction "A_1") (pintype "passive"))
      (node (ref "D13") (pin "2") (pinfunction "K_2") (pintype "passive"))
      (node (ref "P6") (pin "1") (pinfunction "1_1") (pintype "passive"))
    )
    (net (code "43") (name "Net-(D12-A)") (class "Default")
      (node (ref "D12") (pin "1") (pinfunction "A_1") (pintype "passive"))
      (node (ref "D14") (pin "2") (pinfunction "K_2") (pintype "passive"))
      (node (ref "P6") (pin "2") (pinfunction "2_2") (pintype "passive"))
    )
    (net (code "44") (name "Net-(D15-A)") (class "Default")
      (node (ref "D15") (pin "1") (pinfunction "A_1") (pintype "passive"))
      (node (ref "R32") (pin "2") (pinfunction "2_2") (pintype "passive"))
    )
    (net (code "45") (name "Net-(D16-A)") (class "Default")
      (node (ref "D16") (pin "1") (pinfunction "A_1") (pintype "passive"))
      (node (ref "D18") (pin "2") (pinfunction "K_2") (pintype "passive"))
      (node (ref "P8") (pin "2") (pinfunction "2_2") (pintype "passive"))
    )
    (net (code "46") (name "Net-(D16-K)") (class "Default")
      (node (ref "D16") (pin "2") (pinfunction "K_2") (pintype "passive"))
      (node (ref "D17") (pin "2") (pinfunction "K_2") (pintype "passive"))
      (node (ref "R37") (pin "2") (pinfunction "2_2") (pintype "passive"))
    )
    (net (code "47") (name "Net-(D17-A)") (class "Default")
      (node (ref "D17") (pin "1") (pinfunction "A_1") (pintype "passive"))
      (node (ref "D19") (pin "2") (pinfunction "K_2") (pintype "passive"))
      (node (ref "P8") (pin "1") (pinfunction "1_1") (pintype "passive"))
    )
    (net (code "48") (name "Net-(Q1-B)") (class "Default")
      (node (ref "Q1") (pin "1") (pinfunction "B_1") (pintype "passive"))
      (node (ref "R22") (pin "2") (pinfunction "2_2") (pintype "passive"))
      (node (ref "R25") (pin "2") (pinfunction "2_2") (pintype "passive"))
    )
    (net (code "49") (name "Net-(Q2-B)") (class "Default")
      (node (ref "Q2") (pin "1") (pinfunction "B_1") (pintype "passive"))
      (node (ref "R30") (pin "1") (pinfunction "1_1") (pintype "passive"))
    )
    (net (code "50") (name "Net-(Q3-B)") (class "Default")
      (node (ref "Q3") (pin "1") (pinfunction "B_1") (pintype "passive"))
      (node (ref "R40") (pin "1") (pinfunction "1_1") (pintype "passive"))
    )
    (net (code "51") (name "Net-(R4-Pad2)") (class "Default")
      (node (ref "R4") (pin "2") (pinfunction "2_2") (pintype "passive"))
      (node (ref "R5") (pin "1") (pinfunction "1_1") (pintype "passive"))
    )
    (net (code "52") (name "Net-(R5-Pad2)") (class "Default")
      (node (ref "R5") (pin "2") (pinfunction "2_2") (pintype "passive"))
      (node (ref "R6") (pin "1") (pinfunction "1_1") (pintype "passive"))
    )
    (net (code "53") (name "Net-(R8-Pad2)") (class "Default")
      (node (ref "R8") (pin "2") (pinfunction "2_2") (pintype "passive"))
      (node (ref "R9") (pin "1") (pinfunction "1_1") (pintype "passive"))
    )
    (net (code "54") (name "Net-(R10-Pad1)") (class "Default")
      (node (ref "R10") (pin "1") (pinfunction "1_1") (pintype "passive"))
      (node (ref "R9") (pin "2") (pinfunction "2_2") (pintype "passive"))
    )
    (net (code "55") (name "Net-(R14-Pad2)") (class "Default")
      (node (ref "R14") (pin "2") (pinfunction "2_2") (pintype "passive"))
      (node (ref "R15") (pin "1") (pinfunction "1_1") (pintype "passive"))
    )
    (net (code "56") (name "Net-(R16-Pad2)") (class "Default")
      (node (ref "R16") (pin "2") (pinfunction "2_2") (pintype "passive"))
      (node (ref "R17") (pin "1") (pinfunction "1_1") (pintype "passive"))
    )
    (net (code "57") (name "Net-(R17-Pad2)") (class "Default")
      (node (ref "R17") (pin "2") (pinfunction "2_2") (pintype "passive"))
      (node (ref "U4") (pin "6") (pinfunction "6_6") (pintype "passive"))
    )
    (net (code "58") (name "Net-(R18-Pad2)") (class "Default")
      (node (ref "R18") (pin "2") (pinfunction "2_2") (pintype "passive"))
      (node (ref "U4") (pin "1") (pinfunction "1_1") (pintype "passive"))
    )
    (net (code "59") (name "Net-(R23-Pad1)") (class "Default")
      (node (ref "R23") (pin "1") (pinfunction "1_1") (pintype "passive"))
      (node (ref "R24") (pin "2") (pinfunction "2_2") (pintype "passive"))
    )
    (net (code "60") (name "Net-(R26-Pad1)") (class "Default")
      (node (ref "R26") (pin "1") (pinfunction "1_1") (pintype "passive"))
      (node (ref "R27") (pin "2") (pinfunction "2_2") (pintype "passive"))
    )
    (net (code "61") (name "Net-(U1-A)") (class "Default")
      (node (ref "R1") (pin "1") (pinfunction "1_1") (pintype "passive"))
      (node (ref "U1") (pin "1") (pinfunction "A_1") (pintype "passive"))
    )
    (net (code "62") (name "Net-(U1-E)") (class "Default")
      (node (ref "R7") (pin "2") (pinfunction "2_2") (pintype "passive"))
      (node (ref "U1") (pin "3") (pinfunction "E_3") (pintype "passive"))
    )
    (net (code "63") (name "Net-(U1-K)") (class "Default")
      (node (ref "U1") (pin "2") (pinfunction "K_2") (pintype "passive"))
      (node (ref "U2") (pin "1") (pinfunction "OUTA_1") (pintype "output"))
    )
    (net (code "64") (name "Net-(U2A-INA+)") (class "Default")
      (node (ref "R12") (pin "2") (pinfunction "2_2") (pintype "passive"))
      (node (ref "R2") (pin "1") (pinfunction "1_1") (pintype "passive"))
      (node (ref "U2") (pin "3") (pinfunction "INA+_3") (pintype "input"))
    )
    (net (code "65") (name "Net-(U3-R)") (class "Default")
      (node (ref "R13") (pin "2") (pinfunction "2_2") (pintype "passive"))
      (node (ref "U3") (pin "1") (pinfunction "R_1") (pintype "tri_state"))
    )
    (net (code "66") (name "Net-(U5-NRST)") (class "Default")
      (node (ref "C5") (pin "1") (pinfunction "1_1") (pintype "passive"))
      (node (ref "U5") (pin "4") (pinfunction "NRST_4") (pintype "bidirectional"))
    )
    (net (code "67") (name "Net-(U5-VDDA)") (class "Default")
      (node (ref "C8") (pin "1") (pinfunction "1_1") (pintype "passive"))
      (node (ref "C9") (pin "1") (pinfunction "1_1") (pintype "passive"))
      (node (ref "R21") (pin "1") (pinfunction "1_1") (pintype "passive"))
      (node (ref "U5") (pin "5") (pinfunction "VDDA_5") (pintype "power_in"))
    )
    (net (code "68") (name "unconnected-(U2B-GND-Pad4)") (class "Default")
      (node (ref "U2") (pin "4") (pinfunction "GND_4") (pintype "power_in"))
    )
    (net (code "69") (name "unconnected-(U2B-OUTB-Pad7)") (class "Default")
      (node (ref "U2") (pin "7") (pinfunction "OUTB_7") (pintype "output"))
    )
    (net (code "70") (name "unconnected-(U2B-V+-Pad8)") (class "Default")
      (node (ref "U2") (pin "8") (pinfunction "V+_8") (pintype "power_in"))
    )
    (net (code "71") (name "unconnected-(U4-Pad3)") (class "Default")
      (node (ref "U4") (pin "3") (pinfunction "3_3") (pintype "passive"))
    )
    (net (code "72") (name "unconnected-(U4-Pad5)") (class "Default")
      (node (ref "U4") (pin "5") (pinfunction "5_5") (pintype "passive"))
    )
  )
)
